# DSPCONN_8-11.net
KiCad netlist of a schematic drawn in Altium Designer
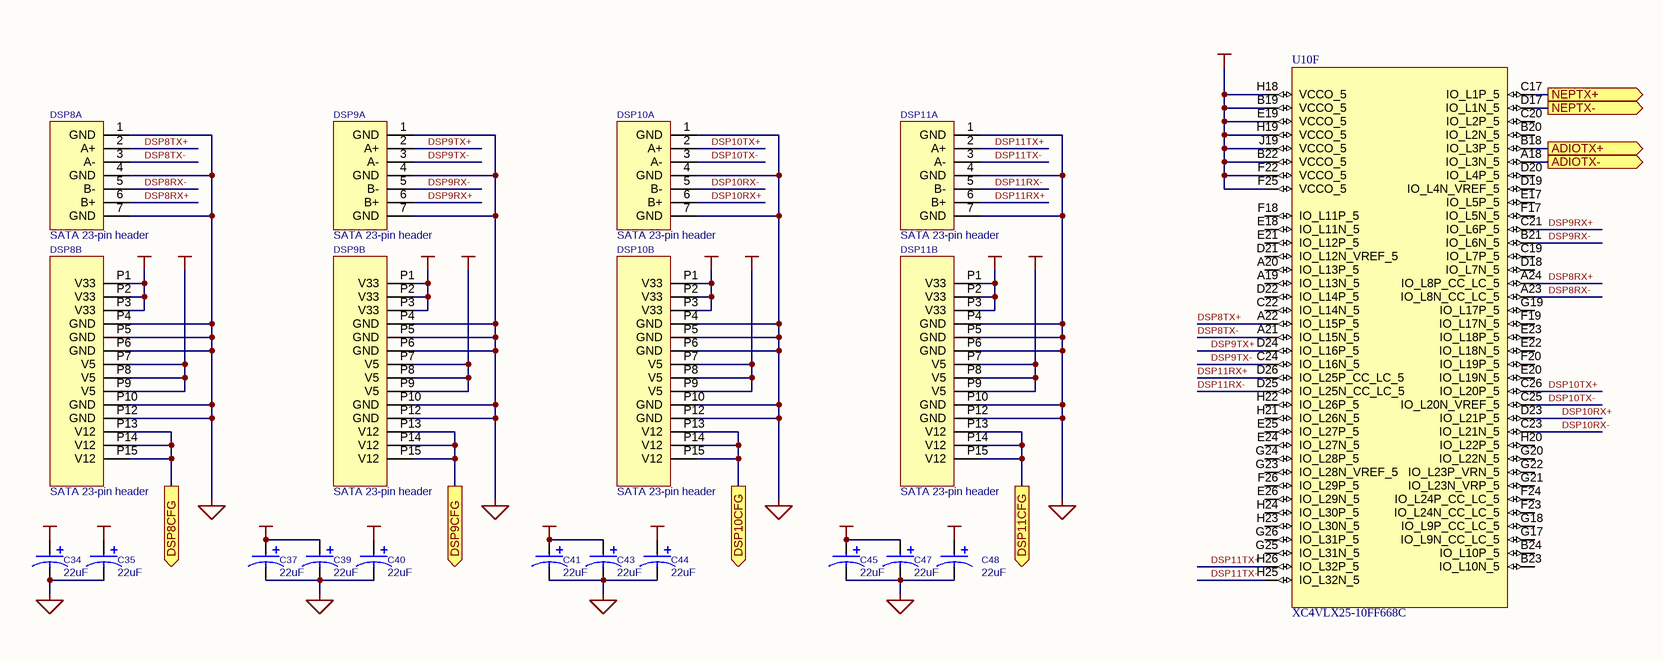
[diagram p0: DSPCONN.8-11.SCHDOC]

(export (version "E")
  (design (tool "Eeschema 10.0.6"))
  (components
    (comp (ref "C34")
      (value "22uF")
      (footprint "6032")
      (description "Standard Capacitor")
      (fields (field (name "Comment") "POLCAP2"))
      (libsource (lib "parts") (part "POLCAP2"))
    )
    (comp (ref "C35")
      (value "22uF")
      (footprint "6032")
      (description "Standard Capacitor")
      (fields (field (name "Comment") "POLCAP2"))
      (libsource (lib "parts") (part "POLCAP2"))
    )
    (comp (ref "C37")
      (value "22uF")
      (footprint "6032")
      (description "Standard Capacitor")
      (fields (field (name "Comment") "POLCAP2"))
      (libsource (lib "parts") (part "POLCAP2"))
    )
    (comp (ref "C39")
      (value "22uF")
      (footprint "6032")
      (description "Standard Capacitor")
      (fields (field (name "Comment") "POLCAP2"))
      (libsource (lib "parts") (part "POLCAP2"))
    )
    (comp (ref "C40")
      (value "22uF")
      (footprint "6032")
      (description "Standard Capacitor")
      (fields (field (name "Comment") "POLCAP2"))
      (libsource (lib "parts") (part "POLCAP2"))
    )
    (comp (ref "C41")
      (value "22uF")
      (footprint "6032")
      (description "Standard Capacitor")
      (fields (field (name "Comment") "POLCAP2"))
      (libsource (lib "parts") (part "POLCAP2"))
    )
    (comp (ref "C43")
      (value "22uF")
      (footprint "6032")
      (description "Standard Capacitor")
      (fields (field (name "Comment") "POLCAP2"))
      (libsource (lib "parts") (part "POLCAP2"))
    )
    (comp (ref "C44")
      (value "22uF")
      (footprint "6032")
      (description "Standard Capacitor")
      (fields (field (name "Comment") "POLCAP2"))
      (libsource (lib "parts") (part "POLCAP2"))
    )
    (comp (ref "C45")
      (value "22uF")
      (footprint "6032")
      (description "Standard Capacitor")
      (fields (field (name "Comment") "POLCAP2"))
      (libsource (lib "parts") (part "POLCAP2"))
    )
    (comp (ref "C47")
      (value "22uF")
      (footprint "6032")
      (description "Standard Capacitor")
      (fields (field (name "Comment") "POLCAP2"))
      (libsource (lib "parts") (part "POLCAP2"))
    )
    (comp (ref "C48")
      (value "22uF")
      (footprint "6032")
      (description "Standard Capacitor")
      (fields (field (name "Comment") "POLCAP2"))
      (libsource (lib "parts") (part "POLCAP2"))
    )
    (comp (ref "DSP8")
      (value "SATA 23-pin header")
      (footprint "MOLEX 87713-1001")
      (libsource (lib "parts") (part "SATA-23"))
    )
    (comp (ref "DSP9")
      (value "SATA 23-pin header")
      (footprint "MOLEX 87713-1001")
      (libsource (lib "parts") (part "SATA-23"))
    )
    (comp (ref "DSP10")
      (value "SATA 23-pin header")
      (footprint "MOLEX 87713-1001")
      (libsource (lib "parts") (part "SATA-23"))
    )
    (comp (ref "DSP11")
      (value "SATA 23-pin header")
      (footprint "MOLEX 87713-1001")
      (libsource (lib "parts") (part "SATA-23"))
    )
    (comp (ref "U10")
      (value "XC4VLX25-10FF668C")
      (footprint "Xilinx FF668")
      (description "Xilinx Virtex-4")
      (libsource (lib "parts") (part "XC4VLX25-10FF668C"))
    )
  )
  (nets
    (net (code "1") (name "+2.5VCC") (class "Default")
      (node (ref "U10") (pin "B19") (pinfunction "VCCO_5_B19") (pintype "bidirectional"))
      (node (ref "U10") (pin "B22") (pinfunction "VCCO_5_B22") (pintype "bidirectional"))
      (node (ref "U10") (pin "E19") (pinfunction "VCCO_5_E19") (pintype "bidirectional"))
      (node (ref "U10") (pin "F22") (pinfunction "VCCO_5_F22") (pintype "bidirectional"))
      (node (ref "U10") (pin "F25") (pinfunction "VCCO_5_F25") (pintype "bidirectional"))
      (node (ref "U10") (pin "H18") (pinfunction "VCCO_5_H18") (pintype "bidirectional"))
      (node (ref "U10") (pin "H19") (pinfunction "VCCO_5_H19") (pintype "bidirectional"))
      (node (ref "U10") (pin "J19") (pinfunction "VCCO_5_J19") (pintype "bidirectional"))
    )
    (net (code "2") (name "+5VCC") (class "Default")
      (node (ref "C35") (pin "1") (pintype "passive"))
      (node (ref "C40") (pin "1") (pintype "passive"))
      (node (ref "C44") (pin "1") (pintype "passive"))
      (node (ref "C48") (pin "1") (pintype "passive"))
      (node (ref "DSP10") (pin "P7") (pinfunction "V5_P7") (pintype "passive"))
      (node (ref "DSP10") (pin "P8") (pinfunction "V5_P8") (pintype "passive"))
      (node (ref "DSP10") (pin "P9") (pinfunction "V5_P9") (pintype "passive"))
      (node (ref "DSP11") (pin "P7") (pinfunction "V5_P7") (pintype "passive"))
      (node (ref "DSP11") (pin "P8") (pinfunction "V5_P8") (pintype "passive"))
      (node (ref "DSP11") (pin "P9") (pinfunction "V5_P9") (pintype "passive"))
      (node (ref "DSP8") (pin "P7") (pinfunction "V5_P7") (pintype "passive"))
      (node (ref "DSP8") (pin "P8") (pinfunction "V5_P8") (pintype "passive"))
      (node (ref "DSP8") (pin "P9") (pinfunction "V5_P9") (pintype "passive"))
      (node (ref "DSP9") (pin "P7") (pinfunction "V5_P7") (pintype "passive"))
      (node (ref "DSP9") (pin "P8") (pinfunction "V5_P8") (pintype "passive"))
      (node (ref "DSP9") (pin "P9") (pinfunction "V5_P9") (pintype "passive"))
    )
    (net (code "3") (name "/ADIOTX+") (class "Default")
      (node (ref "U10") (pin "B18") (pinfunction "IO_L3P_5_B18") (pintype "bidirectional"))
    )
    (net (code "4") (name "/ADIOTX-") (class "Default")
      (node (ref "U10") (pin "A18") (pinfunction "IO_L3N_5_A18") (pintype "bidirectional"))
    )
    (net (code "5") (name "/DSP8CFG") (class "Default")
      (node (ref "DSP8") (pin "P13") (pinfunction "V12_P13") (pintype "passive"))
      (node (ref "DSP8") (pin "P14") (pinfunction "V12_P14") (pintype "passive"))
      (node (ref "DSP8") (pin "P15") (pinfunction "V12_P15") (pintype "passive"))
    )
    (net (code "6") (name "/DSP8RX+") (class "Default")
      (node (ref "DSP8") (pin "6") (pinfunction "B+_6") (pintype "passive"))
      (node (ref "U10") (pin "A24") (pinfunction "IO_L8P_CC_LC_5_A24") (pintype "bidirectional"))
    )
    (net (code "7") (name "/DSP8RX-") (class "Default")
      (node (ref "DSP8") (pin "5") (pinfunction "B-_5") (pintype "passive"))
      (node (ref "U10") (pin "A23") (pinfunction "IO_L8N_CC_LC_5_A23") (pintype "bidirectional"))
    )
    (net (code "8") (name "/DSP8TX+") (class "Default")
      (node (ref "DSP8") (pin "2") (pinfunction "A+_2") (pintype "passive"))
      (node (ref "U10") (pin "A22") (pinfunction "IO_L15P_5_A22") (pintype "bidirectional"))
    )
    (net (code "9") (name "/DSP8TX-") (class "Default")
      (node (ref "DSP8") (pin "3") (pinfunction "A-_3") (pintype "passive"))
      (node (ref "U10") (pin "A21") (pinfunction "IO_L15N_5_A21") (pintype "bidirectional"))
    )
    (net (code "10") (name "/DSP9CFG") (class "Default")
      (node (ref "DSP9") (pin "P13") (pinfunction "V12_P13") (pintype "passive"))
      (node (ref "DSP9") (pin "P14") (pinfunction "V12_P14") (pintype "passive"))
      (node (ref "DSP9") (pin "P15") (pinfunction "V12_P15") (pintype "passive"))
    )
    (net (code "11") (name "/DSP9RX+") (class "Default")
      (node (ref "DSP9") (pin "6") (pinfunction "B+_6") (pintype "passive"))
      (node (ref "U10") (pin "C21") (pinfunction "IO_L6P_5_C21") (pintype "bidirectional"))
    )
    (net (code "12") (name "/DSP9RX-") (class "Default")
      (node (ref "DSP9") (pin "5") (pinfunction "B-_5") (pintype "passive"))
      (node (ref "U10") (pin "B21") (pinfunction "IO_L6N_5_B21") (pintype "bidirectional"))
    )
    (net (code "13") (name "/DSP9TX+") (class "Default")
      (node (ref "DSP9") (pin "2") (pinfunction "A+_2") (pintype "passive"))
      (node (ref "U10") (pin "D24") (pinfunction "IO_L16P_5_D24") (pintype "bidirectional"))
    )
    (net (code "14") (name "/DSP9TX-") (class "Default")
      (node (ref "DSP9") (pin "3") (pinfunction "A-_3") (pintype "passive"))
      (node (ref "U10") (pin "C24") (pinfunction "IO_L16N_5_C24") (pintype "bidirectional"))
    )
    (net (code "15") (name "/DSP10CFG") (class "Default")
      (node (ref "DSP10") (pin "P13") (pinfunction "V12_P13") (pintype "passive"))
      (node (ref "DSP10") (pin "P14") (pinfunction "V12_P14") (pintype "passive"))
      (node (ref "DSP10") (pin "P15") (pinfunction "V12_P15") (pintype "passive"))
    )
    (net (code "16") (name "/DSP10RX+") (class "Default")
      (node (ref "DSP10") (pin "6") (pinfunction "B+_6") (pintype "passive"))
      (node (ref "U10") (pin "D23") (pinfunction "IO_L21P_5_D23") (pintype "bidirectional"))
    )
    (net (code "17") (name "/DSP10RX-") (class "Default")
      (node (ref "DSP10") (pin "5") (pinfunction "B-_5") (pintype "passive"))
      (node (ref "U10") (pin "C23") (pinfunction "IO_L21N_5_C23") (pintype "bidirectional"))
    )
    (net (code "18") (name "/DSP10TX+") (class "Default")
      (node (ref "DSP10") (pin "2") (pinfunction "A+_2") (pintype "passive"))
      (node (ref "U10") (pin "C26") (pinfunction "IO_L20P_5_C26") (pintype "bidirectional"))
    )
    (net (code "19") (name "/DSP10TX-") (class "Default")
      (node (ref "DSP10") (pin "3") (pinfunction "A-_3") (pintype "passive"))
      (node (ref "U10") (pin "C25") (pinfunction "IO_L20N_VREF_5_C25") (pintype "bidirectional"))
    )
    (net (code "20") (name "/DSP11CFG") (class "Default")
      (node (ref "DSP11") (pin "P13") (pinfunction "V12_P13") (pintype "passive"))
      (node (ref "DSP11") (pin "P14") (pinfunction "V12_P14") (pintype "passive"))
      (node (ref "DSP11") (pin "P15") (pinfunction "V12_P15") (pintype "passive"))
    )
    (net (code "21") (name "/DSP11RX+") (class "Default")
      (node (ref "DSP11") (pin "6") (pinfunction "B+_6") (pintype "passive"))
      (node (ref "U10") (pin "D26") (pinfunction "IO_L25P_CC_LC_5_D26") (pintype "bidirectional"))
    )
    (net (code "22") (name "/DSP11RX-") (class "Default")
      (node (ref "DSP11") (pin "5") (pinfunction "B-_5") (pintype "passive"))
      (node (ref "U10") (pin "D25") (pinfunction "IO_L25N_CC_LC_5_D25") (pintype "bidirectional"))
    )
    (net (code "23") (name "/DSP11TX+") (class "Default")
      (node (ref "DSP11") (pin "2") (pinfunction "A+_2") (pintype "passive"))
      (node (ref "U10") (pin "H26") (pinfunction "IO_L32P_5_H26") (pintype "bidirectional"))
    )
    (net (code "24") (name "/DSP11TX-") (class "Default")
      (node (ref "DSP11") (pin "3") (pinfunction "A-_3") (pintype "passive"))
      (node (ref "U10") (pin "H25") (pinfunction "IO_L32N_5_H25") (pintype "bidirectional"))
    )
    (net (code "25") (name "/NEPTX+") (class "Default")
      (node (ref "U10") (pin "C17") (pinfunction "IO_L1P_5_C17") (pintype "bidirectional"))
    )
    (net (code "26") (name "/NEPTX-") (class "Default")
      (node (ref "U10") (pin "D17") (pinfunction "IO_L1N_5_D17") (pintype "bidirectional"))
    )
    (net (code "27") (name "GND") (class "Default")
      (node (ref "C34") (pin "2") (pintype "passive"))
      (node (ref "C35") (pin "2") (pintype "passive"))
      (node (ref "C37") (pin "2") (pintype "passive"))
      (node (ref "C39") (pin "2") (pintype "passive"))
      (node (ref "C40") (pin "2") (pintype "passive"))
      (node (ref "C41") (pin "2") (pintype "passive"))
      (node (ref "C43") (pin "2") (pintype "passive"))
      (node (ref "C44") (pin "2") (pintype "passive"))
      (node (ref "C45") (pin "2") (pintype "passive"))
      (node (ref "C47") (pin "2") (pintype "passive"))
      (node (ref "C48") (pin "2") (pintype "passive"))
      (node (ref "DSP10") (pin "1") (pinfunction "GND_1") (pintype "passive"))
      (node (ref "DSP10") (pin "4") (pinfunction "GND_4") (pintype "passive"))
      (node (ref "DSP10") (pin "7") (pinfunction "GND_7") (pintype "passive"))
      (node (ref "DSP10") (pin "P10") (pinfunction "GND_P10") (pintype "passive"))
      (node (ref "DSP10") (pin "P12") (pinfunction "GND_P12") (pintype "passive"))
      (node (ref "DSP10") (pin "P4") (pinfunction "GND_P4") (pintype "passive"))
      (node (ref "DSP10") (pin "P5") (pinfunction "GND_P5") (pintype "passive"))
      (node (ref "DSP10") (pin "P6") (pinfunction "GND_P6") (pintype "passive"))
      (node (ref "DSP11") (pin "1") (pinfunction "GND_1") (pintype "passive"))
      (node (ref "DSP11") (pin "4") (pinfunction "GND_4") (pintype "passive"))
      (node (ref "DSP11") (pin "7") (pinfunction "GND_7") (pintype "passive"))
      (node (ref "DSP11") (pin "P10") (pinfunction "GND_P10") (pintype "passive"))
      (node (ref "DSP11") (pin "P12") (pinfunction "GND_P12") (pintype "passive"))
      (node (ref "DSP11") (pin "P4") (pinfunction "GND_P4") (pintype "passive"))
      (node (ref "DSP11") (pin "P5") (pinfunction "GND_P5") (pintype "passive"))
      (node (ref "DSP11") (pin "P6") (pinfunction "GND_P6") (pintype "passive"))
      (node (ref "DSP8") (pin "1") (pinfunction "GND_1") (pintype "passive"))
      (node (ref "DSP8") (pin "4") (pinfunction "GND_4") (pintype "passive"))
      (node (ref "DSP8") (pin "7") (pinfunction "GND_7") (pintype "passive"))
      (node (ref "DSP8") (pin "P10") (pinfunction "GND_P10") (pintype "passive"))
      (node (ref "DSP8") (pin "P12") (pinfunction "GND_P12") (pintype "passive"))
      (node (ref "DSP8") (pin "P4") (pinfunction "GND_P4") (pintype "passive"))
      (node (ref "DSP8") (pin "P5") (pinfunction "GND_P5") (pintype "passive"))
      (node (ref "DSP8") (pin "P6") (pinfunction "GND_P6") (pintype "passive"))
      (node (ref "DSP9") (pin "1") (pinfunction "GND_1") (pintype "passive"))
      (node (ref "DSP9") (pin "4") (pinfunction "GND_4") (pintype "passive"))
      (node (ref "DSP9") (pin "7") (pinfunction "GND_7") (pintype "passive"))
      (node (ref "DSP9") (pin "P10") (pinfunction "GND_P10") (pintype "passive"))
      (node (ref "DSP9") (pin "P12") (pinfunction "GND_P12") (pintype "passive"))
      (node (ref "DSP9") (pin "P4") (pinfunction "GND_P4") (pintype "passive"))
      (node (ref "DSP9") (pin "P5") (pinfunction "GND_P5") (pintype "passive"))
      (node (ref "DSP9") (pin "P6") (pinfunction "GND_P6") (pintype "passive"))
    )
    (net (code "28") (name "VCC2") (class "Default")
      (node (ref "C34") (pin "1") (pintype "passive"))
      (node (ref "C37") (pin "1") (pintype "passive"))
      (node (ref "C39") (pin "1") (pintype "passive"))
      (node (ref "C41") (pin "1") (pintype "passive"))
      (node (ref "C43") (pin "1") (pintype "passive"))
      (node (ref "C45") (pin "1") (pintype "passive"))
      (node (ref "C47") (pin "1") (pintype "passive"))
      (node (ref "DSP10") (pin "P1") (pinfunction "V33_P1") (pintype "passive"))
      (node (ref "DSP10") (pin "P2") (pinfunction "V33_P2") (pintype "passive"))
      (node (ref "DSP10") (pin "P3") (pinfunction "V33_P3") (pintype "passive"))
      (node (ref "DSP11") (pin "P1") (pinfunction "V33_P1") (pintype "passive"))
      (node (ref "DSP11") (pin "P2") (pinfunction "V33_P2") (pintype "passive"))
      (node (ref "DSP11") (pin "P3") (pinfunction "V33_P3") (pintype "passive"))
      (node (ref "DSP8") (pin "P1") (pinfunction "V33_P1") (pintype "passive"))
      (node (ref "DSP8") (pin "P2") (pinfunction "V33_P2") (pintype "passive"))
      (node (ref "DSP8") (pin "P3") (pinfunction "V33_P3") (pintype "passive"))
      (node (ref "DSP9") (pin "P1") (pinfunction "V33_P1") (pintype "passive"))
      (node (ref "DSP9") (pin "P2") (pinfunction "V33_P2") (pintype "passive"))
      (node (ref "DSP9") (pin "P3") (pinfunction "V33_P3") (pintype "passive"))
    )
    (net (code "29") (name "unconnected-(U10F-IO_L2N_5-PadB20)") (class "Default")
      (node (ref "U10") (pin "B20") (pinfunction "IO_L2N_5_B20") (pintype "bidirectional"))
    )
    (net (code "30") (name "unconnected-(U10F-IO_L2P_5-PadC20)") (class "Default")
      (node (ref "U10") (pin "C20") (pinfunction "IO_L2P_5_C20") (pintype "bidirectional"))
    )
    (net (code "31") (name "unconnected-(U10F-IO_L4N_VREF_5-PadD19)") (class "Default")
      (node (ref "U10") (pin "D19") (pinfunction "IO_L4N_VREF_5_D19") (pintype "bidirectional"))
    )
    (net (code "32") (name "unconnected-(U10F-IO_L4P_5-PadD20)") (class "Default")
      (node (ref "U10") (pin "D20") (pinfunction "IO_L4P_5_D20") (pintype "bidirectional"))
    )
    (net (code "33") (name "unconnected-(U10F-IO_L5N_5-PadF17)") (class "Default")
      (node (ref "U10") (pin "F17") (pinfunction "IO_L5N_5_F17") (pintype "bidirectional"))
    )
    (net (code "34") (name "unconnected-(U10F-IO_L5P_5-PadE17)") (class "Default")
      (node (ref "U10") (pin "E17") (pinfunction "IO_L5P_5_E17") (pintype "bidirectional"))
    )
    (net (code "35") (name "unconnected-(U10F-IO_L7N_5-PadD18)") (class "Default")
      (node (ref "U10") (pin "D18") (pinfunction "IO_L7N_5_D18") (pintype "bidirectional"))
    )
    (net (code "36") (name "unconnected-(U10F-IO_L7P_5-PadC19)") (class "Default")
      (node (ref "U10") (pin "C19") (pinfunction "IO_L7P_5_C19") (pintype "bidirectional"))
    )
    (net (code "37") (name "unconnected-(U10F-IO_L9N_CC_LC_5-PadG17)") (class "Default")
      (node (ref "U10") (pin "G17") (pinfunction "IO_L9N_CC_LC_5_G17") (pintype "bidirectional"))
    )
    (net (code "38") (name "unconnected-(U10F-IO_L9P_CC_LC_5-PadG18)") (class "Default")
      (node (ref "U10") (pin "G18") (pinfunction "IO_L9P_CC_LC_5_G18") (pintype "bidirectional"))
    )
    (net (code "39") (name "unconnected-(U10F-IO_L10N_5-PadB23)") (class "Default")
      (node (ref "U10") (pin "B23") (pinfunction "IO_L10N_5_B23") (pintype "bidirectional"))
    )
    (net (code "40") (name "unconnected-(U10F-IO_L10P_5-PadB24)") (class "Default")
      (node (ref "U10") (pin "B24") (pinfunction "IO_L10P_5_B24") (pintype "bidirectional"))
    )
    (net (code "41") (name "unconnected-(U10F-IO_L11N_5-PadE18)") (class "Default")
      (node (ref "U10") (pin "E18") (pinfunction "IO_L11N_5_E18") (pintype "bidirectional"))
    )
    (net (code "42") (name "unconnected-(U10F-IO_L11P_5-PadF18)") (class "Default")
      (node (ref "U10") (pin "F18") (pinfunction "IO_L11P_5_F18") (pintype "bidirectional"))
    )
    (net (code "43") (name "unconnected-(U10F-IO_L12N_VREF_5-PadD21)") (class "Default")
      (node (ref "U10") (pin "D21") (pinfunction "IO_L12N_VREF_5_D21") (pintype "bidirectional"))
    )
    (net (code "44") (name "unconnected-(U10F-IO_L12P_5-PadE21)") (class "Default")
      (node (ref "U10") (pin "E21") (pinfunction "IO_L12P_5_E21") (pintype "bidirectional"))
    )
    (net (code "45") (name "unconnected-(U10F-IO_L13N_5-PadA19)") (class "Default")
      (node (ref "U10") (pin "A19") (pinfunction "IO_L13N_5_A19") (pintype "bidirectional"))
    )
    (net (code "46") (name "unconnected-(U10F-IO_L13P_5-PadA20)") (class "Default")
      (node (ref "U10") (pin "A20") (pinfunction "IO_L13P_5_A20") (pintype "bidirectional"))
    )
    (net (code "47") (name "unconnected-(U10F-IO_L14N_5-PadC22)") (class "Default")
      (node (ref "U10") (pin "C22") (pinfunction "IO_L14N_5_C22") (pintype "bidirectional"))
    )
    (net (code "48") (name "unconnected-(U10F-IO_L14P_5-PadD22)") (class "Default")
      (node (ref "U10") (pin "D22") (pinfunction "IO_L14P_5_D22") (pintype "bidirectional"))
    )
    (net (code "49") (name "unconnected-(U10F-IO_L17N_5-PadF19)") (class "Default")
      (node (ref "U10") (pin "F19") (pinfunction "IO_L17N_5_F19") (pintype "bidirectional"))
    )
    (net (code "50") (name "unconnected-(U10F-IO_L17P_5-PadG19)") (class "Default")
      (node (ref "U10") (pin "G19") (pinfunction "IO_L17P_5_G19") (pintype "bidirectional"))
    )
    (net (code "51") (name "unconnected-(U10F-IO_L18N_5-PadE22)") (class "Default")
      (node (ref "U10") (pin "E22") (pinfunction "IO_L18N_5_E22") (pintype "bidirectional"))
    )
    (net (code "52") (name "unconnected-(U10F-IO_L18P_5-PadE23)") (class "Default")
      (node (ref "U10") (pin "E23") (pinfunction "IO_L18P_5_E23") (pintype "bidirectional"))
    )
    (net (code "53") (name "unconnected-(U10F-IO_L19N_5-PadE20)") (class "Default")
      (node (ref "U10") (pin "E20") (pinfunction "IO_L19N_5_E20") (pintype "bidirectional"))
    )
    (net (code "54") (name "unconnected-(U10F-IO_L19P_5-PadF20)") (class "Default")
      (node (ref "U10") (pin "F20") (pinfunction "IO_L19P_5_F20") (pintype "bidirectional"))
    )
    (net (code "55") (name "unconnected-(U10F-IO_L22N_5-PadG20)") (class "Default")
      (node (ref "U10") (pin "G20") (pinfunction "IO_L22N_5_G20") (pintype "bidirectional"))
    )
    (net (code "56") (name "unconnected-(U10F-IO_L22P_5-PadH20)") (class "Default")
      (node (ref "U10") (pin "H20") (pinfunction "IO_L22P_5_H20") (pintype "bidirectional"))
    )
    (net (code "57") (name "unconnected-(U10F-IO_L23N_VRP_5-PadG21)") (class "Default")
      (node (ref "U10") (pin "G21") (pinfunction "IO_L23N_VRP_5_G21") (pintype "bidirectional"))
    )
    (net (code "58") (name "unconnected-(U10F-IO_L23P_VRN_5-PadG22)") (class "Default")
      (node (ref "U10") (pin "G22") (pinfunction "IO_L23P_VRN_5_G22") (pintype "bidirectional"))
    )
    (net (code "59") (name "unconnected-(U10F-IO_L24N_CC_LC_5-PadF23)") (class "Default")
      (node (ref "U10") (pin "F23") (pinfunction "IO_L24N_CC_LC_5_F23") (pintype "bidirectional"))
    )
    (net (code "60") (name "unconnected-(U10F-IO_L24P_CC_LC_5-PadF24)") (class "Default")
      (node (ref "U10") (pin "F24") (pinfunction "IO_L24P_CC_LC_5_F24") (pintype "bidirectional"))
    )
    (net (code "61") (name "unconnected-(U10F-IO_L26N_5-PadH21)") (class "Default")
      (node (ref "U10") (pin "H21") (pinfunction "IO_L26N_5_H21") (pintype "bidirectional"))
    )
    (net (code "62") (name "unconnected-(U10F-IO_L26P_5-PadH22)") (class "Default")
      (node (ref "U10") (pin "H22") (pinfunction "IO_L26P_5_H22") (pintype "bidirectional"))
    )
    (net (code "63") (name "unconnected-(U10F-IO_L27N_5-PadE24)") (class "Default")
      (node (ref "U10") (pin "E24") (pinfunction "IO_L27N_5_E24") (pintype "bidirectional"))
    )
    (net (code "64") (name "unconnected-(U10F-IO_L27P_5-PadE25)") (class "Default")
      (node (ref "U10") (pin "E25") (pinfunction "IO_L27P_5_E25") (pintype "bidirectional"))
    )
    (net (code "65") (name "unconnected-(U10F-IO_L28N_VREF_5-PadG23)") (class "Default")
      (node (ref "U10") (pin "G23") (pinfunction "IO_L28N_VREF_5_G23") (pintype "bidirectional"))
    )
    (net (code "66") (name "unconnected-(U10F-IO_L28P_5-PadG24)") (class "Default")
      (node (ref "U10") (pin "G24") (pinfunction "IO_L28P_5_G24") (pintype "bidirectional"))
    )
    (net (code "67") (name "unconnected-(U10F-IO_L29N_5-PadE26)") (class "Default")
      (node (ref "U10") (pin "E26") (pinfunction "IO_L29N_5_E26") (pintype "bidirectional"))
    )
    (net (code "68") (name "unconnected-(U10F-IO_L29P_5-PadF26)") (class "Default")
      (node (ref "U10") (pin "F26") (pinfunction "IO_L29P_5_F26") (pintype "bidirectional"))
    )
    (net (code "69") (name "unconnected-(U10F-IO_L30N_5-PadH23)") (class "Default")
      (node (ref "U10") (pin "H23") (pinfunction "IO_L30N_5_H23") (pintype "bidirectional"))
    )
    (net (code "70") (name "unconnected-(U10F-IO_L30P_5-PadH24)") (class "Default")
      (node (ref "U10") (pin "H24") (pinfunction "IO_L30P_5_H24") (pintype "bidirectional"))
    )
    (net (code "71") (name "unconnected-(U10F-IO_L31N_5-PadG25)") (class "Default")
      (node (ref "U10") (pin "G25") (pinfunction "IO_L31N_5_G25") (pintype "bidirectional"))
    )
    (net (code "72") (name "unconnected-(U10F-IO_L31P_5-PadG26)") (class "Default")
      (node (ref "U10") (pin "G26") (pinfunction "IO_L31P_5_G26") (pintype "bidirectional"))
    )
  )
)
